# MicArraySchem_V3.net
KiCad netlist of a schematic drawn in Altium Designer
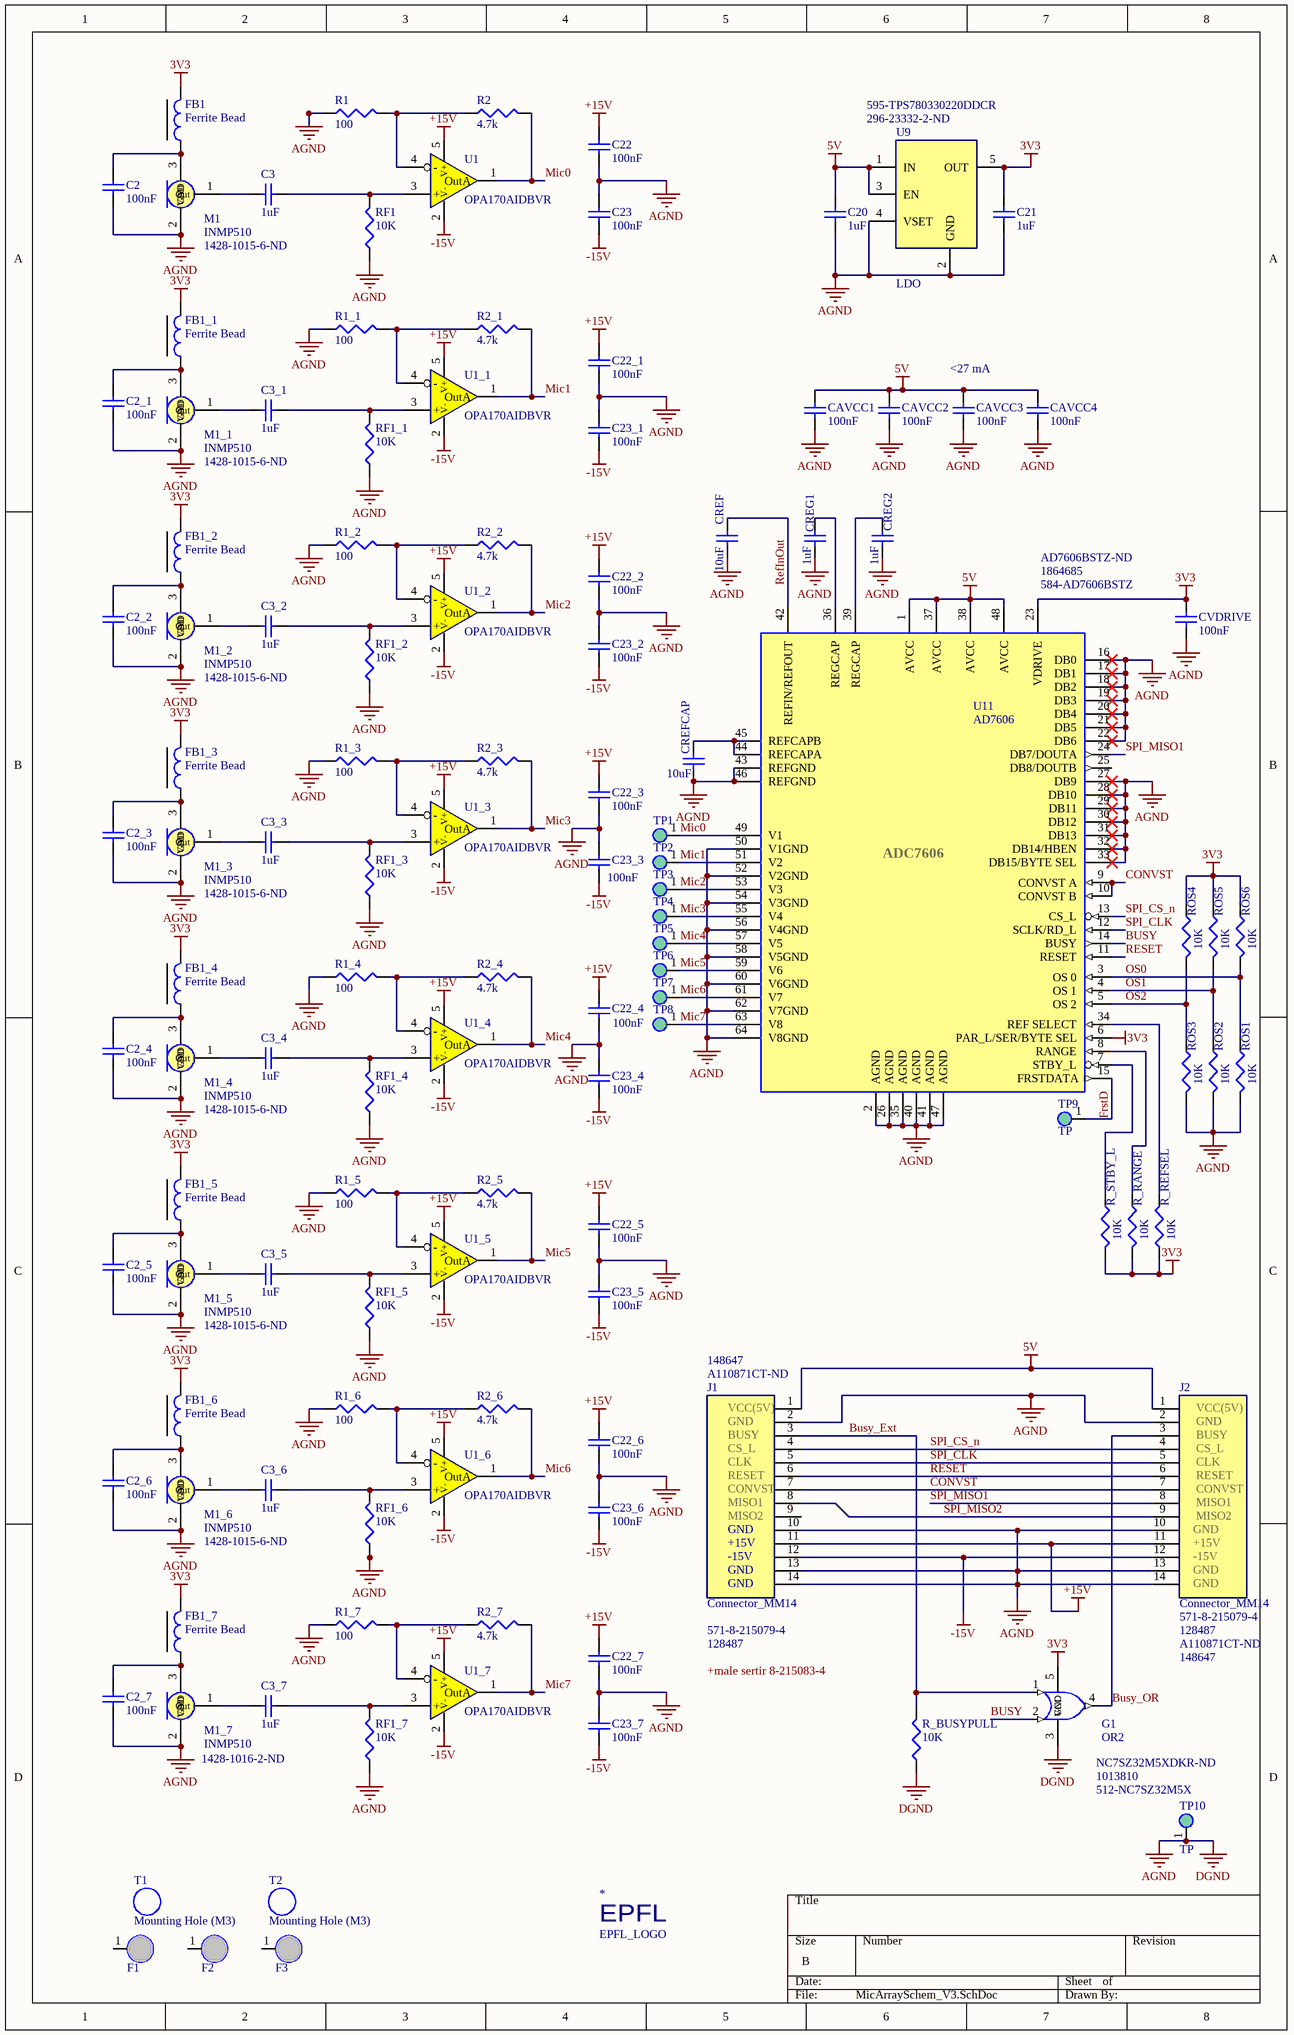
[diagram p0: MicArraySchem_V3.SchDoc]

(export (version "E")
  (design (tool "Eeschema 10.0.6"))
  (components
    (comp (ref "*")
      (value "EPFL_LOGO")
      (footprint "EPFL_Logo")
      (libsource (lib "HEPIA_LSN_RB_V1") (part "EPFL_LOGO"))
    )
    (comp (ref "C2")
      (value "100nF")
      (footprint "1608[0603]")
      (description "Capacitor (Semiconductor SIM Model)")
      (fields (field (name "PUBLISHER") "Altium Limited"))
      (libsource (lib "Miscellaneous Devices") (part "Cap Semi"))
    )
    (comp (ref "C2_1")
      (value "100nF")
      (footprint "1608[0603]")
      (description "Capacitor (Semiconductor SIM Model)")
      (fields (field (name "PUBLISHER") "Altium Limited"))
      (libsource (lib "Miscellaneous Devices") (part "Cap Semi"))
    )
    (comp (ref "C2_2")
      (value "100nF")
      (footprint "1608[0603]")
      (description "Capacitor (Semiconductor SIM Model)")
      (fields (field (name "PUBLISHER") "Altium Limited"))
      (libsource (lib "Miscellaneous Devices") (part "Cap Semi"))
    )
    (comp (ref "C2_3")
      (value "100nF")
      (footprint "1608[0603]")
      (description "Capacitor (Semiconductor SIM Model)")
      (fields (field (name "PUBLISHER") "Altium Limited"))
      (libsource (lib "Miscellaneous Devices") (part "Cap Semi"))
    )
    (comp (ref "C2_4")
      (value "100nF")
      (footprint "1608[0603]")
      (description "Capacitor (Semiconductor SIM Model)")
      (fields (field (name "PUBLISHER") "Altium Limited"))
      (libsource (lib "Miscellaneous Devices") (part "Cap Semi"))
    )
    (comp (ref "C2_5")
      (value "100nF")
      (footprint "1608[0603]")
      (description "Capacitor (Semiconductor SIM Model)")
      (fields (field (name "PUBLISHER") "Altium Limited"))
      (libsource (lib "Miscellaneous Devices") (part "Cap Semi"))
    )
    (comp (ref "C2_6")
      (value "100nF")
      (footprint "1608[0603]")
      (description "Capacitor (Semiconductor SIM Model)")
      (fields (field (name "PUBLISHER") "Altium Limited"))
      (libsource (lib "Miscellaneous Devices") (part "Cap Semi"))
    )
    (comp (ref "C2_7")
      (value "100nF")
      (footprint "1608[0603]")
      (description "Capacitor (Semiconductor SIM Model)")
      (fields (field (name "PUBLISHER") "Altium Limited"))
      (libsource (lib "Miscellaneous Devices") (part "Cap Semi"))
    )
    (comp (ref "C3")
      (value "1uF")
      (footprint "1608[0603]")
      (description "Capacitor (Semiconductor SIM Model)")
      (libsource (lib "Miscellaneous Devices") (part "Cap Semi"))
    )
    (comp (ref "C3_1")
      (value "1uF")
      (footprint "1608[0603]")
      (description "Capacitor (Semiconductor SIM Model)")
      (fields (field (name "PUBLISHER") "Altium Limited"))
      (libsource (lib "Miscellaneous Devices") (part "Cap Semi"))
    )
    (comp (ref "C3_2")
      (value "1uF")
      (footprint "1608[0603]")
      (description "Capacitor (Semiconductor SIM Model)")
      (fields (field (name "PUBLISHER") "Altium Limited"))
      (libsource (lib "Miscellaneous Devices") (part "Cap Semi"))
    )
    (comp (ref "C3_3")
      (value "1uF")
      (footprint "1608[0603]")
      (description "Capacitor (Semiconductor SIM Model)")
      (fields (field (name "PUBLISHER") "Altium Limited"))
      (libsource (lib "Miscellaneous Devices") (part "Cap Semi"))
    )
    (comp (ref "C3_4")
      (value "1uF")
      (footprint "1608[0603]")
      (description "Capacitor (Semiconductor SIM Model)")
      (fields (field (name "PUBLISHER") "Altium Limited"))
      (libsource (lib "Miscellaneous Devices") (part "Cap Semi"))
    )
    (comp (ref "C3_5")
      (value "1uF")
      (footprint "1608[0603]")
      (description "Capacitor (Semiconductor SIM Model)")
      (fields (field (name "PUBLISHER") "Altium Limited"))
      (libsource (lib "Miscellaneous Devices") (part "Cap Semi"))
    )
    (comp (ref "C3_6")
      (value "1uF")
      (footprint "1608[0603]")
      (description "Capacitor (Semiconductor SIM Model)")
      (fields (field (name "PUBLISHER") "Altium Limited"))
      (libsource (lib "Miscellaneous Devices") (part "Cap Semi"))
    )
    (comp (ref "C3_7")
      (value "1uF")
      (footprint "1608[0603]")
      (description "Capacitor (Semiconductor SIM Model)")
      (fields (field (name "PUBLISHER") "Altium Limited"))
      (libsource (lib "Miscellaneous Devices") (part "Cap Semi"))
    )
    (comp (ref "C20")
      (value "1uF")
      (footprint "1608[0603]")
      (description "Capacitor (Semiconductor SIM Model)")
      (fields (field (name "PUBLISHER") "Altium Limited"))
      (libsource (lib "Miscellaneous Devices") (part "Cap Semi"))
    )
    (comp (ref "C21")
      (value "1uF")
      (footprint "1608[0603]")
      (description "Capacitor (Semiconductor SIM Model)")
      (fields (field (name "PUBLISHER") "Altium Limited"))
      (libsource (lib "Miscellaneous Devices") (part "Cap Semi"))
    )
    (comp (ref "C22")
      (value "100nF")
      (footprint "1608[0603]")
      (description "Capacitor (Semiconductor SIM Model)")
      (fields (field (name "PUBLISHER") "Altium Limited"))
      (libsource (lib "Miscellaneous Devices") (part "Cap Semi"))
    )
    (comp (ref "C22_1")
      (value "100nF")
      (footprint "1608[0603]")
      (description "Capacitor (Semiconductor SIM Model)")
      (fields (field (name "PUBLISHER") "Altium Limited"))
      (libsource (lib "Miscellaneous Devices") (part "Cap Semi"))
    )
    (comp (ref "C22_2")
      (value "100nF")
      (footprint "1608[0603]")
      (description "Capacitor (Semiconductor SIM Model)")
      (fields (field (name "PUBLISHER") "Altium Limited"))
      (libsource (lib "Miscellaneous Devices") (part "Cap Semi"))
    )
    (comp (ref "C22_3")
      (value "100nF")
      (footprint "1608[0603]")
      (description "Capacitor (Semiconductor SIM Model)")
      (fields (field (name "PUBLISHER") "Altium Limited"))
      (libsource (lib "Miscellaneous Devices") (part "Cap Semi"))
    )
    (comp (ref "C22_4")
      (value "100nF")
      (footprint "1608[0603]")
      (description "Capacitor (Semiconductor SIM Model)")
      (fields (field (name "PUBLISHER") "Altium Limited"))
      (libsource (lib "Miscellaneous Devices") (part "Cap Semi"))
    )
    (comp (ref "C22_5")
      (value "100nF")
      (footprint "1608[0603]")
      (description "Capacitor (Semiconductor SIM Model)")
      (fields (field (name "PUBLISHER") "Altium Limited"))
      (libsource (lib "Miscellaneous Devices") (part "Cap Semi"))
    )
    (comp (ref "C22_6")
      (value "100nF")
      (footprint "1608[0603]")
      (description "Capacitor (Semiconductor SIM Model)")
      (fields (field (name "PUBLISHER") "Altium Limited"))
      (libsource (lib "Miscellaneous Devices") (part "Cap Semi"))
    )
    (comp (ref "C22_7")
      (value "100nF")
      (footprint "1608[0603]")
      (description "Capacitor (Semiconductor SIM Model)")
      (fields (field (name "PUBLISHER") "Altium Limited"))
      (libsource (lib "Miscellaneous Devices") (part "Cap Semi"))
    )
    (comp (ref "C23")
      (value "100nF")
      (footprint "1608[0603]")
      (description "Capacitor (Semiconductor SIM Model)")
      (fields (field (name "PUBLISHER") "Altium Limited"))
      (libsource (lib "Miscellaneous Devices") (part "Cap Semi"))
    )
    (comp (ref "C23_1")
      (value "100nF")
      (footprint "1608[0603]")
      (description "Capacitor (Semiconductor SIM Model)")
      (fields (field (name "PUBLISHER") "Altium Limited"))
      (libsource (lib "Miscellaneous Devices") (part "Cap Semi"))
    )
    (comp (ref "C23_2")
      (value "100nF")
      (footprint "1608[0603]")
      (description "Capacitor (Semiconductor SIM Model)")
      (fields (field (name "PUBLISHER") "Altium Limited"))
      (libsource (lib "Miscellaneous Devices") (part "Cap Semi"))
    )
    (comp (ref "C23_3")
      (value "100nF")
      (footprint "1608[0603]")
      (description "Capacitor (Semiconductor SIM Model)")
      (fields (field (name "PUBLISHER") "Altium Limited"))
      (libsource (lib "Miscellaneous Devices") (part "Cap Semi"))
    )
    (comp (ref "C23_4")
      (value "100nF")
      (footprint "1608[0603]")
      (description "Capacitor (Semiconductor SIM Model)")
      (fields (field (name "PUBLISHER") "Altium Limited"))
      (libsource (lib "Miscellaneous Devices") (part "Cap Semi"))
    )
    (comp (ref "C23_5")
      (value "100nF")
      (footprint "1608[0603]")
      (description "Capacitor (Semiconductor SIM Model)")
      (fields (field (name "PUBLISHER") "Altium Limited"))
      (libsource (lib "Miscellaneous Devices") (part "Cap Semi"))
    )
    (comp (ref "C23_6")
      (value "100nF")
      (footprint "1608[0603]")
      (description "Capacitor (Semiconductor SIM Model)")
      (fields (field (name "PUBLISHER") "Altium Limited"))
      (libsource (lib "Miscellaneous Devices") (part "Cap Semi"))
    )
    (comp (ref "C23_7")
      (value "100nF")
      (footprint "1608[0603]")
      (description "Capacitor (Semiconductor SIM Model)")
      (fields (field (name "PUBLISHER") "Altium Limited"))
      (libsource (lib "Miscellaneous Devices") (part "Cap Semi"))
    )
    (comp (ref "CAVCC1")
      (value "100nF")
      (footprint "1608[0603]")
      (description "Capacitor (Semiconductor SIM Model)")
      (fields (field (name "PUBLISHER") "Altium Limited"))
      (libsource (lib "Miscellaneous Devices") (part "Cap Semi"))
    )
    (comp (ref "CAVCC2")
      (value "100nF")
      (footprint "1608[0603]")
      (description "Capacitor (Semiconductor SIM Model)")
      (fields (field (name "PUBLISHER") "Altium Limited"))
      (libsource (lib "Miscellaneous Devices") (part "Cap Semi"))
    )
    (comp (ref "CAVCC3")
      (value "100nF")
      (footprint "1608[0603]")
      (description "Capacitor (Semiconductor SIM Model)")
      (fields (field (name "PUBLISHER") "Altium Limited"))
      (libsource (lib "Miscellaneous Devices") (part "Cap Semi"))
    )
    (comp (ref "CAVCC4")
      (value "100nF")
      (footprint "1608[0603]")
      (description "Capacitor (Semiconductor SIM Model)")
      (fields (field (name "PUBLISHER") "Altium Limited"))
      (libsource (lib "Miscellaneous Devices") (part "Cap Semi"))
    )
    (comp (ref "CREF")
      (value "10uF")
      (footprint "1608[0603]")
      (description "Capacitor (Semiconductor SIM Model)")
      (fields (field (name "PUBLISHER") "Altium Limited"))
      (libsource (lib "Miscellaneous Devices") (part "Cap Semi"))
    )
    (comp (ref "CREFCAP")
      (value "10uF")
      (footprint "1608[0603]")
      (description "Capacitor (Semiconductor SIM Model)")
      (fields (field (name "PUBLISHER") "Altium Limited"))
      (libsource (lib "Miscellaneous Devices") (part "Cap Semi"))
    )
    (comp (ref "CREG1")
      (value "1uF")
      (footprint "1608[0603]")
      (description "Capacitor (Semiconductor SIM Model)")
      (fields (field (name "PUBLISHER") "Altium Limited"))
      (libsource (lib "Miscellaneous Devices") (part "Cap Semi"))
    )
    (comp (ref "CREG2")
      (value "1uF")
      (footprint "1608[0603]")
      (description "Capacitor (Semiconductor SIM Model)")
      (fields (field (name "PUBLISHER") "Altium Limited"))
      (libsource (lib "Miscellaneous Devices") (part "Cap Semi"))
    )
    (comp (ref "CVDRIVE")
      (value "100nF")
      (footprint "1608[0603]")
      (description "Capacitor (Semiconductor SIM Model)")
      (fields (field (name "PUBLISHER") "Altium Limited"))
      (libsource (lib "Miscellaneous Devices") (part "Cap Semi"))
    )
    (comp (ref "F1") (value "*") (footprint "Fiducial_round_2mm") (libsource (lib "Lab2") (part "Reference")))
    (comp (ref "F2") (value "*") (footprint "Fiducial_round_2mm") (libsource (lib "Lab2") (part "Reference")))
    (comp (ref "F3") (value "*") (footprint "Fiducial_round_2mm") (libsource (lib "Lab2") (part "Reference")))
    (comp (ref "FB1")
      (value "Ferrite Bead")
      (footprint "HEPIA_LSN_RB_V1:L_0603")
      (description "Ferrite bead.")
      (libsource (lib "MicArraySchemComponents") (part "Ferrite Bead"))
    )
    (comp (ref "FB1_1")
      (value "Ferrite Bead")
      (footprint "L_0603")
      (description "Ferrite bead.")
      (libsource (lib "MicArraySchemComponents") (part "Ferrite Bead"))
    )
    (comp (ref "FB1_2")
      (value "Ferrite Bead")
      (footprint "L_0603")
      (description "Ferrite bead.")
      (libsource (lib "MicArraySchemComponents") (part "Ferrite Bead"))
    )
    (comp (ref "FB1_3")
      (value "Ferrite Bead")
      (footprint "L_0603")
      (description "Ferrite bead.")
      (libsource (lib "MicArraySchemComponents") (part "Ferrite Bead"))
    )
    (comp (ref "FB1_4")
      (value "Ferrite Bead")
      (footprint "L_0603")
      (description "Ferrite bead.")
      (libsource (lib "MicArraySchemComponents") (part "Ferrite Bead"))
    )
    (comp (ref "FB1_5")
      (value "Ferrite Bead")
      (footprint "L_0603")
      (description "Ferrite bead.")
      (libsource (lib "MicArraySchemComponents") (part "Ferrite Bead"))
    )
    (comp (ref "FB1_6")
      (value "Ferrite Bead")
      (footprint "L_0603")
      (description "Ferrite bead.")
      (libsource (lib "MicArraySchemComponents") (part "Ferrite Bead"))
    )
    (comp (ref "FB1_7")
      (value "Ferrite Bead")
      (footprint "L_0603")
      (description "Ferrite bead.")
      (libsource (lib "MicArraySchemComponents") (part "Ferrite Bead"))
    )
    (comp (ref "G1")
      (value "OR2")
      (footprint "SOT65P210X110-5N")
      (description "TinyOR2")
      (fields
        (field (name "SUPPLIER PART NUMBER 1") "512-NC7SZ32M5X")
        (field (name "SUPPLIER PART NUMBER 2") "1013810")
        (field (name "SUPPLIER PART NUMBER 3") "NC7SZ32M5XDKR-ND")
      )
      (libsource (lib "MicArraySchemComponents") (part "OR2"))
    )
    (comp (ref "J1")
      (value "Connector_MM14")
      (footprint "MM14 _TH_FEMALE")
      (fields
        (field (name "SUPPLIER PART NUMBER 2") "571-8-215079-4")
        (field (name "SUPPLIER PART NUMBER 4") "128487")
        (field (name "SUPPLIER PART NUMBER 3") "A110871CT-ND")
        (field (name "SUPPLIER PART NUMBER 1") "148647")
      )
      (libsource (lib "MicArraySchemComponents") (part "Connector_MM14"))
    )
    (comp (ref "J2")
      (value "Connector_MM14")
      (footprint "MM14 _TH_FEMALE")
      (fields
        (field (name "SUPPLIER PART NUMBER 2") "571-8-215079-4")
        (field (name "SUPPLIER PART NUMBER 4") "128487")
        (field (name "SUPPLIER PART NUMBER 3") "A110871CT-ND")
        (field (name "SUPPLIER PART NUMBER 1") "148647")
      )
      (libsource (lib "") (part "Connector_MM14_1"))
    )
    (comp (ref "M1")
      (value "INMP510")
      (footprint "INMP504")
      (description "INMP504")
      (fields (field (name "SUPPLIER PART NUMBER 1") "1428-1015-6-ND"))
      (libsource (lib "MicArraySchemComponents") (part "Mic"))
    )
    (comp (ref "M1_1")
      (value "INMP510")
      (footprint "INMP504")
      (description "INMP504")
      (fields (field (name "SUPPLIER PART NUMBER 1") "1428-1015-6-ND"))
      (libsource (lib "MicArraySchemComponents") (part "Mic"))
    )
    (comp (ref "M1_2")
      (value "INMP510")
      (footprint "INMP504")
      (description "INMP504")
      (fields (field (name "SUPPLIER PART NUMBER 1") "1428-1015-6-ND"))
      (libsource (lib "MicArraySchemComponents") (part "Mic"))
    )
    (comp (ref "M1_3")
      (value "INMP510")
      (footprint "INMP504")
      (description "INMP504")
      (fields (field (name "SUPPLIER PART NUMBER 1") "1428-1015-6-ND"))
      (libsource (lib "MicArraySchemComponents") (part "Mic"))
    )
    (comp (ref "M1_4")
      (value "INMP510")
      (footprint "INMP504")
      (description "INMP504")
      (fields (field (name "SUPPLIER PART NUMBER 1") "1428-1015-6-ND"))
      (libsource (lib "MicArraySchemComponents") (part "Mic"))
    )
    (comp (ref "M1_5")
      (value "INMP510")
      (footprint "INMP504")
      (description "INMP504")
      (fields (field (name "SUPPLIER PART NUMBER 1") "1428-1015-6-ND"))
      (libsource (lib "MicArraySchemComponents") (part "Mic"))
    )
    (comp (ref "M1_6")
      (value "INMP510")
      (footprint "INMP504")
      (description "INMP504")
      (fields (field (name "SUPPLIER PART NUMBER 1") "1428-1015-6-ND"))
      (libsource (lib "MicArraySchemComponents") (part "Mic"))
    )
    (comp (ref "M1_7")
      (value "INMP510")
      (footprint "INMP504")
      (description "INMP504")
      (fields (field (name "SUPPLIER PART NUMBER 1") "1428-1016-2-ND"))
      (libsource (lib "MicArraySchemComponents") (part "Mic"))
    )
    (comp (ref "R1")
      (value "100")
      (footprint "J1-0603")
      (description "Resistor")
      (fields (field (name "PUBLISHER") "Altium Limited"))
      (libsource (lib "Miscellaneous Devices") (part "Res3"))
    )
    (comp (ref "R1_1")
      (value "100")
      (footprint "J1-0603")
      (description "Resistor")
      (fields (field (name "PUBLISHER") "Altium Limited"))
      (libsource (lib "Miscellaneous Devices") (part "Res3"))
    )
    (comp (ref "R1_2")
      (value "100")
      (footprint "J1-0603")
      (description "Resistor")
      (fields (field (name "PUBLISHER") "Altium Limited"))
      (libsource (lib "Miscellaneous Devices") (part "Res3"))
    )
    (comp (ref "R1_3")
      (value "100")
      (footprint "J1-0603")
      (description "Resistor")
      (fields (field (name "PUBLISHER") "Altium Limited"))
      (libsource (lib "Miscellaneous Devices") (part "Res3"))
    )
    (comp (ref "R1_4")
      (value "100")
      (footprint "J1-0603")
      (description "Resistor")
      (fields (field (name "PUBLISHER") "Altium Limited"))
      (libsource (lib "Miscellaneous Devices") (part "Res3"))
    )
    (comp (ref "R1_5")
      (value "100")
      (footprint "J1-0603")
      (description "Resistor")
      (fields (field (name "PUBLISHER") "Altium Limited"))
      (libsource (lib "Miscellaneous Devices") (part "Res3"))
    )
    (comp (ref "R1_6")
      (value "100")
      (footprint "J1-0603")
      (description "Resistor")
      (fields (field (name "PUBLISHER") "Altium Limited"))
      (libsource (lib "Miscellaneous Devices") (part "Res3"))
    )
    (comp (ref "R1_7")
      (value "100")
      (footprint "J1-0603")
      (description "Resistor")
      (fields (field (name "PUBLISHER") "Altium Limited"))
      (libsource (lib "Miscellaneous Devices") (part "Res3"))
    )
    (comp (ref "R2")
      (value "4.7k")
      (footprint "J1-0603")
      (description "Resistor")
      (fields (field (name "PUBLISHER") "Altium Limited"))
      (libsource (lib "Miscellaneous Devices") (part "Res3"))
    )
    (comp (ref "R2_1")
      (value "4.7k")
      (footprint "J1-0603")
      (description "Resistor")
      (fields (field (name "PUBLISHER") "Altium Limited"))
      (libsource (lib "Miscellaneous Devices") (part "Res3"))
    )
    (comp (ref "R2_2")
      (value "4.7k")
      (footprint "J1-0603")
      (description "Resistor")
      (fields (field (name "PUBLISHER") "Altium Limited"))
      (libsource (lib "Miscellaneous Devices") (part "Res3"))
    )
    (comp (ref "R2_3")
      (value "4.7k")
      (footprint "J1-0603")
      (description "Resistor")
      (fields (field (name "PUBLISHER") "Altium Limited"))
      (libsource (lib "Miscellaneous Devices") (part "Res3"))
    )
    (comp (ref "R2_4")
      (value "4.7k")
      (footprint "J1-0603")
      (description "Resistor")
      (fields (field (name "PUBLISHER") "Altium Limited"))
      (libsource (lib "Miscellaneous Devices") (part "Res3"))
    )
    (comp (ref "R2_5")
      (value "4.7k")
      (footprint "J1-0603")
      (description "Resistor")
      (fields (field (name "PUBLISHER") "Altium Limited"))
      (libsource (lib "Miscellaneous Devices") (part "Res3"))
    )
    (comp (ref "R2_6")
      (value "4.7k")
      (footprint "J1-0603")
      (description "Resistor")
      (fields (field (name "PUBLISHER") "Altium Limited"))
      (libsource (lib "Miscellaneous Devices") (part "Res3"))
    )
    (comp (ref "R2_7")
      (value "4.7k")
      (footprint "J1-0603")
      (description "Resistor")
      (fields (field (name "PUBLISHER") "Altium Limited"))
      (libsource (lib "Miscellaneous Devices") (part "Res3"))
    )
    (comp (ref "RF1")
      (value "10K")
      (footprint "J1-0603")
      (description "Resistor")
      (fields (field (name "PUBLISHER") "Altium Limited"))
      (libsource (lib "Miscellaneous Devices") (part "Res3"))
    )
    (comp (ref "RF1_1")
      (value "10K")
      (footprint "J1-0603")
      (description "Resistor")
      (fields (field (name "PUBLISHER") "Altium Limited"))
      (libsource (lib "Miscellaneous Devices") (part "Res3"))
    )
    (comp (ref "RF1_2")
      (value "10K")
      (footprint "J1-0603")
      (description "Resistor")
      (fields (field (name "PUBLISHER") "Altium Limited"))
      (libsource (lib "Miscellaneous Devices") (part "Res3"))
    )
    (comp (ref "RF1_3")
      (value "10K")
      (footprint "J1-0603")
      (description "Resistor")
      (fields (field (name "PUBLISHER") "Altium Limited"))
      (libsource (lib "Miscellaneous Devices") (part "Res3"))
    )
    (comp (ref "RF1_4")
      (value "10K")
      (footprint "J1-0603")
      (description "Resistor")
      (fields (field (name "PUBLISHER") "Altium Limited"))
      (libsource (lib "Miscellaneous Devices") (part "Res3"))
    )
    (comp (ref "RF1_5")
      (value "10K")
      (footprint "J1-0603")
      (description "Resistor")
      (fields (field (name "PUBLISHER") "Altium Limited"))
      (libsource (lib "Miscellaneous Devices") (part "Res3"))
    )
    (comp (ref "RF1_6")
      (value "10K")
      (footprint "J1-0603")
      (description "Resistor")
      (fields (field (name "PUBLISHER") "Altium Limited"))
      (libsource (lib "Miscellaneous Devices") (part "Res3"))
    )
    (comp (ref "RF1_7")
      (value "10K")
      (footprint "J1-0603")
      (description "Resistor")
      (fields (field (name "PUBLISHER") "Altium Limited"))
      (libsource (lib "Miscellaneous Devices") (part "Res3"))
    )
    (comp (ref "ROS1")
      (value "10K")
      (footprint "J1-0603")
      (description "Resistor")
      (fields (field (name "PUBLISHER") "Altium Limited"))
      (libsource (lib "Miscellaneous Devices") (part "Res3"))
    )
    (comp (ref "ROS2")
      (value "10K")
      (footprint "J1-0603")
      (description "Resistor")
      (fields (field (name "PUBLISHER") "Altium Limited"))
      (libsource (lib "Miscellaneous Devices") (part "Res3"))
    )
    (comp (ref "ROS3")
      (value "10K")
      (footprint "J1-0603")
      (description "Resistor")
      (fields (field (name "PUBLISHER") "Altium Limited"))
      (libsource (lib "Miscellaneous Devices") (part "Res3"))
    )
    (comp (ref "ROS4")
      (value "10K")
      (footprint "J1-0603")
      (description "Resistor")
      (fields (field (name "PUBLISHER") "Altium Limited"))
      (libsource (lib "Miscellaneous Devices") (part "Res3"))
    )
    (comp (ref "ROS5")
      (value "10K")
      (footprint "J1-0603")
      (description "Resistor")
      (fields (field (name "PUBLISHER") "Altium Limited"))
      (libsource (lib "Miscellaneous Devices") (part "Res3"))
    )
    (comp (ref "ROS6")
      (value "10K")
      (footprint "J1-0603")
      (description "Resistor")
      (fields (field (name "PUBLISHER") "Altium Limited"))
      (libsource (lib "Miscellaneous Devices") (part "Res3"))
    )
    (comp (ref "R_BUSYPULL")
      (value "10K")
      (footprint "J1-0603")
      (description "Resistor")
      (fields (field (name "PUBLISHER") "Altium Limited"))
      (libsource (lib "Miscellaneous Devices") (part "Res3"))
    )
    (comp (ref "R_RANGE")
      (value "10K")
      (footprint "J1-0603")
      (description "Resistor")
      (fields (field (name "PUBLISHER") "Altium Limited"))
      (libsource (lib "Miscellaneous Devices") (part "Res3"))
    )
    (comp (ref "R_REFSEL")
      (value "10K")
      (footprint "J1-0603")
      (description "Resistor")
      (fields (field (name "PUBLISHER") "Altium Limited"))
      (libsource (lib "Miscellaneous Devices") (part "Res3"))
    )
    (comp (ref "R_STBY_L")
      (value "10K")
      (footprint "J1-0603")
      (description "Resistor")
      (fields (field (name "PUBLISHER") "Altium Limited"))
      (libsource (lib "Miscellaneous Devices") (part "Res3"))
    )
    (comp (ref "T1")
      (value "Mounting Hole (M3)")
      (footprint "M3MountingHole")
      (libsource (lib "MicArraySchemComponents") (part "Mounting Hole (M3)"))
    )
    (comp (ref "T2")
      (value "Mounting Hole (M3)")
      (footprint "M3MountingHole")
      (libsource (lib "MicArraySchemComponents") (part "Mounting Hole (M3)"))
    )
    (comp (ref "TP1") (value "TP") (footprint "TP_0.75mm") (libsource (lib "HEPIA_LSN_RB_V1") (part "TP")))
    (comp (ref "TP2") (value "TP") (footprint "TP_0.75mm") (libsource (lib "HEPIA_LSN_RB_V1") (part "TP")))
    (comp (ref "TP3") (value "TP") (footprint "TP_0.75mm") (libsource (lib "HEPIA_LSN_RB_V1") (part "TP")))
    (comp (ref "TP4") (value "TP") (footprint "TP_0.75mm") (libsource (lib "HEPIA_LSN_RB_V1") (part "TP")))
    (comp (ref "TP5") (value "TP") (footprint "TP_0.75mm") (libsource (lib "HEPIA_LSN_RB_V1") (part "TP")))
    (comp (ref "TP6") (value "TP") (footprint "TP_0.75mm") (libsource (lib "HEPIA_LSN_RB_V1") (part "TP")))
    (comp (ref "TP7") (value "TP") (footprint "TP_0.75mm") (libsource (lib "HEPIA_LSN_RB_V1") (part "TP")))
    (comp (ref "TP8") (value "TP") (footprint "TP_0.75mm") (libsource (lib "HEPIA_LSN_RB_V1") (part "TP")))
    (comp (ref "TP9") (value "TP") (footprint "TP_0.75mm") (libsource (lib "HEPIA_LSN_RB_V1") (part "TP")))
    (comp (ref "TP10") (value "TP") (footprint "TP_1mm") (libsource (lib "HEPIA_LSN_RB_V1") (part "TP")))
    (comp (ref "U1")
      (value "OPA170AIDBVR")
      (footprint "SOT95P280X145-5N")
      (description "OPA170")
      (libsource (lib "MicArraySchemComponents") (part "OPA170"))
    )
    (comp (ref "U1_1")
      (value "OPA170AIDBVR")
      (footprint "SOT95P280X145-5N")
      (description "OPA170")
      (libsource (lib "MicArraySchemComponents") (part "OPA170"))
    )
    (comp (ref "U1_2")
      (value "OPA170AIDBVR")
      (footprint "SOT95P280X145-5N")
      (description "OPA170")
      (libsource (lib "MicArraySchemComponents") (part "OPA170"))
    )
    (comp (ref "U1_3")
      (value "OPA170AIDBVR")
      (footprint "SOT95P280X145-5N")
      (description "OPA170")
      (libsource (lib "MicArraySchemComponents") (part "OPA170"))
    )
    (comp (ref "U1_4")
      (value "OPA170AIDBVR")
      (footprint "SOT95P280X145-5N")
      (description "OPA170")
      (libsource (lib "MicArraySchemComponents") (part "OPA170"))
    )
    (comp (ref "U1_5")
      (value "OPA170AIDBVR")
      (footprint "SOT95P280X145-5N")
      (description "OPA170")
      (libsource (lib "MicArraySchemComponents") (part "OPA170"))
    )
    (comp (ref "U1_6")
      (value "OPA170AIDBVR")
      (footprint "SOT95P280X145-5N")
      (description "OPA170")
      (libsource (lib "MicArraySchemComponents") (part "OPA170"))
    )
    (comp (ref "U1_7")
      (value "OPA170AIDBVR")
      (footprint "SOT95P280X145-5N")
      (description "OPA170")
      (libsource (lib "MicArraySchemComponents") (part "OPA170"))
    )
    (comp (ref "U9")
      (value "LDO")
      (footprint "SOT95P280X110-5N")
      (description "TPS780330220DDCR")
      (fields
        (field (name "SUPPLIER PART NUMBER 1") "296-23332-2-ND")
        (field (name "SUPPLIER PART NUMBER 2") "595-TPS780330220DDCR")
      )
      (libsource (lib "MicArraySchemComponents") (part "LDO"))
    )
    (comp (ref "U11")
      (value "AD7606")
      (footprint "LPQF-Quad64")
      (fields
        (field (name "SUPPLIER PART NUMBER 1") "AD7606BSTZ-ND")
        (field (name "SUPPLIER PART NUMBER 2") "1864685")
        (field (name "SUPPLIER PART NUMBER 3") "584-AD7606BSTZ")
      )
      (libsource (lib "MicArraySchemComponents") (part "AD7606"))
    )
  )
  (nets
    (net (code "1") (name "+15V") (class "Default")
      (node (ref "C22") (pin "1") (pinfunction "1_1") (pintype "passive"))
      (node (ref "C22_1") (pin "1") (pinfunction "1_1") (pintype "passive"))
      (node (ref "C22_2") (pin "1") (pinfunction "1_1") (pintype "passive"))
      (node (ref "C22_3") (pin "1") (pinfunction "1_1") (pintype "passive"))
      (node (ref "C22_4") (pin "1") (pinfunction "1_1") (pintype "passive"))
      (node (ref "C22_5") (pin "1") (pinfunction "1_1") (pintype "passive"))
      (node (ref "C22_6") (pin "1") (pinfunction "1_1") (pintype "passive"))
      (node (ref "C22_7") (pin "1") (pinfunction "1_1") (pintype "passive"))
      (node (ref "J1") (pin "11") (pinfunction "11_11") (pintype "passive"))
      (node (ref "J2") (pin "11") (pinfunction "11_11") (pintype "passive"))
      (node (ref "U1") (pin "5") (pinfunction "V+_5") (pintype "power_in"))
      (node (ref "U1_1") (pin "5") (pinfunction "V+_5") (pintype "power_in"))
      (node (ref "U1_2") (pin "5") (pinfunction "V+_5") (pintype "power_in"))
      (node (ref "U1_3") (pin "5") (pinfunction "V+_5") (pintype "power_in"))
      (node (ref "U1_4") (pin "5") (pinfunction "V+_5") (pintype "power_in"))
      (node (ref "U1_5") (pin "5") (pinfunction "V+_5") (pintype "power_in"))
      (node (ref "U1_6") (pin "5") (pinfunction "V+_5") (pintype "power_in"))
      (node (ref "U1_7") (pin "5") (pinfunction "V+_5") (pintype "power_in"))
    )
    (net (code "2") (name "-15V") (class "Default")
      (node (ref "C23") (pin "2") (pinfunction "2_2") (pintype "passive"))
      (node (ref "C23_1") (pin "2") (pinfunction "2_2") (pintype "passive"))
      (node (ref "C23_2") (pin "2") (pinfunction "2_2") (pintype "passive"))
      (node (ref "C23_3") (pin "2") (pinfunction "2_2") (pintype "passive"))
      (node (ref "C23_4") (pin "2") (pinfunction "2_2") (pintype "passive"))
      (node (ref "C23_5") (pin "2") (pinfunction "2_2") (pintype "passive"))
      (node (ref "C23_6") (pin "2") (pinfunction "2_2") (pintype "passive"))
      (node (ref "C23_7") (pin "2") (pinfunction "2_2") (pintype "passive"))
      (node (ref "J1") (pin "12") (pinfunction "12_12") (pintype "passive"))
      (node (ref "J2") (pin "12") (pinfunction "12_12") (pintype "passive"))
      (node (ref "U1") (pin "2") (pinfunction "V-_2") (pintype "power_in"))
      (node (ref "U1_1") (pin "2") (pinfunction "V-_2") (pintype "power_in"))
      (node (ref "U1_2") (pin "2") (pinfunction "V-_2") (pintype "power_in"))
      (node (ref "U1_3") (pin "2") (pinfunction "V-_2") (pintype "power_in"))
      (node (ref "U1_4") (pin "2") (pinfunction "V-_2") (pintype "power_in"))
      (node (ref "U1_5") (pin "2") (pinfunction "V-_2") (pintype "power_in"))
      (node (ref "U1_6") (pin "2") (pinfunction "V-_2") (pintype "power_in"))
      (node (ref "U1_7") (pin "2") (pinfunction "V-_2") (pintype "power_in"))
    )
    (net (code "3") (name "/BUSY") (class "Default")
      (node (ref "G1") (pin "2") (pintype "input"))
      (node (ref "U11") (pin "14") (pinfunction "BUSY_14") (pintype "output"))
    )
    (net (code "4") (name "/Busy_Ext") (class "Default")
      (node (ref "G1") (pin "1") (pintype "input"))
      (node (ref "J1") (pin "3") (pinfunction "3_3") (pintype "passive"))
      (node (ref "R_BUSYPULL") (pin "2") (pinfunction "2_2") (pintype "passive"))
    )
    (net (code "5") (name "/Busy_OR") (class "Default")
      (node (ref "G1") (pin "4") (pintype "output"))
      (node (ref "J2") (pin "3") (pinfunction "3_3") (pintype "passive"))
    )
    (net (code "6") (name "/CONVST") (class "Default")
      (node (ref "J1") (pin "7") (pinfunction "7_7") (pintype "passive"))
      (node (ref "J2") (pin "7") (pinfunction "7_7") (pintype "passive"))
      (node (ref "U11") (pin "10") (pinfunction "CONVST_B_10") (pintype "input"))
      (node (ref "U11") (pin "9") (pinfunction "CONVST_A_9") (pintype "input"))
    )
    (net (code "7") (name "/FrstD") (class "Default")
      (node (ref "TP9") (pin "1") (pinfunction "TP_1") (pintype "passive"))
      (node (ref "U11") (pin "15") (pinfunction "FRSTDATA_15") (pintype "output"))
    )
    (net (code "8") (name "/Mic0") (class "Default")
      (node (ref "R2") (pin "2") (pinfunction "2_2") (pintype "passive"))
      (node (ref "TP1") (pin "1") (pinfunction "TP_1") (pintype "passive"))
      (node (ref "U1") (pin "1") (pinfunction "OutA_1") (pintype "passive"))
      (node (ref "U11") (pin "49") (pinfunction "V1_49") (pintype "passive"))
    )
    (net (code "9") (name "/Mic1") (class "Default")
      (node (ref "R2_1") (pin "2") (pinfunction "2_2") (pintype "passive"))
      (node (ref "TP2") (pin "1") (pinfunction "TP_1") (pintype "passive"))
      (node (ref "U11") (pin "51") (pinfunction "V2_51") (pintype "passive"))
      (node (ref "U1_1") (pin "1") (pinfunction "OutA_1") (pintype "passive"))
    )
    (net (code "10") (name "/Mic2") (class "Default")
      (node (ref "R2_2") (pin "2") (pinfunction "2_2") (pintype "passive"))
      (node (ref "TP3") (pin "1") (pinfunction "TP_1") (pintype "passive"))
      (node (ref "U11") (pin "53") (pinfunction "V3_53") (pintype "passive"))
      (node (ref "U1_2") (pin "1") (pinfunction "OutA_1") (pintype "passive"))
    )
    (net (code "11") (name "/Mic3") (class "Default")
      (node (ref "R2_3") (pin "2") (pinfunction "2_2") (pintype "passive"))
      (node (ref "TP4") (pin "1") (pinfunction "TP_1") (pintype "passive"))
      (node (ref "U11") (pin "55") (pinfunction "V4_55") (pintype "passive"))
      (node (ref "U1_3") (pin "1") (pinfunction "OutA_1") (pintype "passive"))
    )
    (net (code "12") (name "/Mic4") (class "Default")
      (node (ref "R2_4") (pin "2") (pinfunction "2_2") (pintype "passive"))
      (node (ref "TP5") (pin "1") (pinfunction "TP_1") (pintype "passive"))
      (node (ref "U11") (pin "57") (pinfunction "V5_57") (pintype "passive"))
      (node (ref "U1_4") (pin "1") (pinfunction "OutA_1") (pintype "passive"))
    )
    (net (code "13") (name "/Mic5") (class "Default")
      (node (ref "R2_5") (pin "2") (pinfunction "2_2") (pintype "passive"))
      (node (ref "TP6") (pin "1") (pinfunction "TP_1") (pintype "passive"))
      (node (ref "U11") (pin "59") (pinfunction "V6_59") (pintype "passive"))
      (node (ref "U1_5") (pin "1") (pinfunction "OutA_1") (pintype "passive"))
    )
    (net (code "14") (name "/Mic6") (class "Default")
      (node (ref "R2_6") (pin "2") (pinfunction "2_2") (pintype "passive"))
      (node (ref "TP7") (pin "1") (pinfunction "TP_1") (pintype "passive"))
      (node (ref "U11") (pin "61") (pinfunction "V7_61") (pintype "passive"))
      (node (ref "U1_6") (pin "1") (pinfunction "OutA_1") (pintype "passive"))
    )
    (net (code "15") (name "/Mic7") (class "Default")
      (node (ref "R2_7") (pin "2") (pinfunction "2_2") (pintype "passive"))
      (node (ref "TP8") (pin "1") (pinfunction "TP_1") (pintype "passive"))
      (node (ref "U11") (pin "63") (pinfunction "V8_63") (pintype "passive"))
      (node (ref "U1_7") (pin "1") (pinfunction "OutA_1") (pintype "passive"))
    )
    (net (code "16") (name "/OS0") (class "Default")
      (node (ref "ROS1") (pin "1") (pinfunction "1_1") (pintype "passive"))
      (node (ref "ROS6") (pin "2") (pinfunction "2_2") (pintype "passive"))
      (node (ref "U11") (pin "3") (pinfunction "OS_0_3") (pintype "input"))
    )
    (net (code "17") (name "/OS1") (class "Default")
      (node (ref "ROS2") (pin "1") (pinfunction "1_1") (pintype "passive"))
      (node (ref "ROS5") (pin "2") (pinfunction "2_2") (pintype "passive"))
      (node (ref "U11") (pin "4") (pinfunction "OS_1_4") (pintype "input"))
    )
    (net (code "18") (name "/OS2") (class "Default")
      (node (ref "ROS3") (pin "1") (pinfunction "1_1") (pintype "passive"))
      (node (ref "ROS4") (pin "2") (pinfunction "2_2") (pintype "passive"))
      (node (ref "U11") (pin "5") (pinfunction "OS_2_5") (pintype "input"))
    )
    (net (code "19") (name "/RESET") (class "Default")
      (node (ref "J1") (pin "6") (pinfunction "6_6") (pintype "passive"))
      (node (ref "J2") (pin "6") (pinfunction "6_6") (pintype "passive"))
      (node (ref "U11") (pin "11") (pinfunction "RESET_11") (pintype "input"))
    )
    (net (code "20") (name "/RefInOut") (class "Default")
      (node (ref "CREF") (pin "2") (pinfunction "2_2") (pintype "passive"))
      (node (ref "U11") (pin "42") (pinfunction "REFIN/REFOUT_42") (pintype "power_in"))
    )
    (net (code "21") (name "/SPI_CLK") (class "Default")
      (node (ref "J1") (pin "5") (pinfunction "5_5") (pintype "passive"))
      (node (ref "J2") (pin "5") (pinfunction "5_5") (pintype "passive"))
      (node (ref "U11") (pin "12") (pinfunction "SCLK/RD_L_12") (pintype "input"))
    )
    (net (code "22") (name "/SPI_CS_n") (class "Default")
      (node (ref "J1") (pin "4") (pinfunction "4_4") (pintype "passive"))
      (node (ref "J2") (pin "4") (pinfunction "4_4") (pintype "passive"))
      (node (ref "U11") (pin "13") (pinfunction "CS_L_13") (pintype "input"))
    )
    (net (code "23") (name "/SPI_MISO1") (class "Default")
      (node (ref "J2") (pin "8") (pinfunction "8_8") (pintype "passive"))
      (node (ref "U11") (pin "24") (pinfunction "DB7/DOUTA_24") (pintype "output"))
    )
    (net (code "24") (name "/SPI_MISO2") (class "Default")
      (node (ref "J1") (pin "8") (pinfunction "8_8") (pintype "passive"))
      (node (ref "J2") (pin "9") (pinfunction "9_9") (pintype "passive"))
    )
    (net (code "25") (name "3V3") (class "Default")
      (node (ref "C21") (pin "2") (pinfunction "2_2") (pintype "passive"))
      (node (ref "CVDRIVE") (pin "1") (pinfunction "1_1") (pintype "passive"))
      (node (ref "FB1") (pin "2") (pintype "passive"))
      (node (ref "FB1_1") (pin "2") (pintype "passive"))
      (node (ref "FB1_2") (pin "2") (pintype "passive"))
      (node (ref "FB1_3") (pin "2") (pintype "passive"))
      (node (ref "FB1_4") (pin "2") (pintype "passive"))
      (node (ref "FB1_5") (pin "2") (pintype "passive"))
      (node (ref "FB1_6") (pin "2") (pintype "passive"))
      (node (ref "FB1_7") (pin "2") (pintype "passive"))
      (node (ref "G1") (pin "5") (pinfunction "VCC_5") (pintype "power_in"))
      (node (ref "ROS4") (pin "1") (pinfunction "1_1") (pintype "passive"))
      (node (ref "ROS5") (pin "1") (pinfunction "1_1") (pintype "passive"))
      (node (ref "ROS6") (pin "1") (pinfunction "1_1") (pintype "passive"))
      (node (ref "R_RANGE") (pin "2") (pinfunction "2_2") (pintype "passive"))
      (node (ref "R_REFSEL") (pin "1") (pinfunction "1_1") (pintype "passive"))
      (node (ref "R_STBY_L") (pin "2") (pinfunction "2_2") (pintype "passive"))
      (node (ref "U11") (pin "23") (pinfunction "VDRIVE_23") (pintype "power_in"))
      (node (ref "U11") (pin "6") (pinfunction "PAR_L/SER/BYTE_SEL_6") (pintype "input"))
      (node (ref "U9") (pin "5") (pinfunction "OUT_5") (pintype "passive"))
    )
    (net (code "26") (name "5V") (class "Default")
      (node (ref "C20") (pin "2") (pinfunction "2_2") (pintype "passive"))
      (node (ref "CAVCC1") (pin "2") (pinfunction "2_2") (pintype "passive"))
      (node (ref "CAVCC2") (pin "2") (pinfunction "2_2") (pintype "passive"))
      (node (ref "CAVCC3") (pin "2") (pinfunction "2_2") (pintype "passive"))
      (node (ref "CAVCC4") (pin "2") (pinfunction "2_2") (pintype "passive"))
      (node (ref "J1") (pin "1") (pinfunction "1_1") (pintype "passive"))
      (node (ref "J2") (pin "1") (pinfunction "1_1") (pintype "passive"))
      (node (ref "U11") (pin "1") (pinfunction "AVCC_1") (pintype "power_in"))
      (node (ref "U11") (pin "37") (pinfunction "AVCC_37") (pintype "power_in"))
      (node (ref "U11") (pin "38") (pinfunction "AVCC_38") (pintype "power_in"))
      (node (ref "U11") (pin "48") (pinfunction "AVCC_48") (pintype "power_in"))
      (node (ref "U9") (pin "1") (pinfunction "IN_1") (pintype "power_in"))
      (node (ref "U9") (pin "3") (pinfunction "EN_3") (pintype "passive"))
    )
    (net (code "27") (name "AGND") (class "Default")
      (node (ref "C2") (pin "1") (pinfunction "1_1") (pintype "passive"))
      (node (ref "C20") (pin "1") (pinfunction "1_1") (pintype "passive"))
      (node (ref "C21") (pin "1") (pinfunction "1_1") (pintype "passive"))
      (node (ref "C22") (pin "2") (pinfunction "2_2") (pintype "passive"))
      (node (ref "C22_1") (pin "2") (pinfunction "2_2") (pintype "passive"))
      (node (ref "C22_2") (pin "2") (pinfunction "2_2") (pintype "passive"))
      (node (ref "C22_3") (pin "2") (pinfunction "2_2") (pintype "passive"))
      (node (ref "C22_4") (pin "2") (pinfunction "2_2") (pintype "passive"))
      (node (ref "C22_5") (pin "2") (pinfunction "2_2") (pintype "passive"))
      (node (ref "C22_6") (pin "2") (pinfunction "2_2") (pintype "passive"))
      (node (ref "C22_7") (pin "2") (pinfunction "2_2") (pintype "passive"))
      (node (ref "C23") (pin "1") (pinfunction "1_1") (pintype "passive"))
      (node (ref "C23_1") (pin "1") (pinfunction "1_1") (pintype "passive"))
      (node (ref "C23_2") (pin "1") (pinfunction "1_1") (pintype "passive"))
      (node (ref "C23_3") (pin "1") (pinfunction "1_1") (pintype "passive"))
      (node (ref "C23_4") (pin "1") (pinfunction "1_1") (pintype "passive"))
      (node (ref "C23_5") (pin "1") (pinfunction "1_1") (pintype "passive"))
      (node (ref "C23_6") (pin "1") (pinfunction "1_1") (pintype "passive"))
      (node (ref "C23_7") (pin "1") (pinfunction "1_1") (pintype "passive"))
      (node (ref "C2_1") (pin "1") (pinfunction "1_1") (pintype "passive"))
      (node (ref "C2_2") (pin "1") (pinfunction "1_1") (pintype "passive"))
      (node (ref "C2_3") (pin "1") (pinfunction "1_1") (pintype "passive"))
      (node (ref "C2_4") (pin "1") (pinfunction "1_1") (pintype "passive"))
      (node (ref "C2_5") (pin "1") (pinfunction "1_1") (pintype "passive"))
      (node (ref "C2_6") (pin "1") (pinfunction "1_1") (pintype "passive"))
      (node (ref "C2_7") (pin "1") (pinfunction "1_1") (pintype "passive"))
      (node (ref "CAVCC1") (pin "1") (pinfunction "1_1") (pintype "passive"))
      (node (ref "CAVCC2") (pin "1") (pinfunction "1_1") (pintype "passive"))
      (node (ref "CAVCC3") (pin "1") (pinfunction "1_1") (pintype "passive"))
      (node (ref "CAVCC4") (pin "1") (pinfunction "1_1") (pintype "passive"))
      (node (ref "CREF") (pin "1") (pinfunction "1_1") (pintype "passive"))
      (node (ref "CREFCAP") (pin "1") (pinfunction "1_1") (pintype "passive"))
      (node (ref "CREG1") (pin "1") (pinfunction "1_1") (pintype "passive"))
      (node (ref "CREG2") (pin "1") (pinfunction "1_1") (pintype "passive"))
      (node (ref "CVDRIVE") (pin "2") (pinfunction "2_2") (pintype "passive"))
      (node (ref "G1") (pin "3") (pinfunction "GND_3") (pintype "power_in"))
      (node (ref "J1") (pin "10") (pinfunction "10_10") (pintype "passive"))
      (node (ref "J1") (pin "13") (pinfunction "13_13") (pintype "passive"))
      (node (ref "J1") (pin "14") (pinfunction "14_14") (pintype "passive"))
      (node (ref "J1") (pin "2") (pinfunction "2_2") (pintype "passive"))
      (node (ref "J2") (pin "10") (pinfunction "10_10") (pintype "passive"))
      (node (ref "J2") (pin "13") (pinfunction "13_13") (pintype "passive"))
      (node (ref "J2") (pin "14") (pinfunction "14_14") (pintype "passive"))
      (node (ref "J2") (pin "2") (pinfunction "2_2") (pintype "passive"))
      (node (ref "M1") (pin "2") (pinfunction "GND_2") (pintype "passive"))
      (node (ref "M1_1") (pin "2") (pinfunction "GND_2") (pintype "passive"))
      (node (ref "M1_2") (pin "2") (pinfunction "GND_2") (pintype "passive"))
      (node (ref "M1_3") (pin "2") (pinfunction "GND_2") (pintype "passive"))
      (node (ref "M1_4") (pin "2") (pinfunction "GND_2") (pintype "passive"))
      (node (ref "M1_5") (pin "2") (pinfunction "GND_2") (pintype "passive"))
      (node (ref "M1_6") (pin "2") (pinfunction "GND_2") (pintype "passive"))
      (node (ref "M1_7") (pin "2") (pinfunction "GND_2") (pintype "passive"))
      (node (ref "R1") (pin "1") (pinfunction "1_1") (pintype "passive"))
      (node (ref "R1_1") (pin "1") (pinfunction "1_1") (pintype "passive"))
      (node (ref "R1_2") (pin "1") (pinfunction "1_1") (pintype "passive"))
      (node (ref "R1_3") (pin "1") (pinfunction "1_1") (pintype "passive"))
      (node (ref "R1_4") (pin "1") (pinfunction "1_1") (pintype "passive"))
      (node (ref "R1_5") (pin "1") (pinfunction "1_1") (pintype "passive"))
      (node (ref "R1_6") (pin "1") (pinfunction "1_1") (pintype "passive"))
      (node (ref "R1_7") (pin "1") (pinfunction "1_1") (pintype "passive"))
      (node (ref "RF1") (pin "1") (pinfunction "1_1") (pintype "passive"))
      (node (ref "RF1_1") (pin "1") (pinfunction "1_1") (pintype "passive"))
      (node (ref "RF1_2") (pin "1") (pinfunction "1_1") (pintype "passive"))
      (node (ref "RF1_3") (pin "1") (pinfunction "1_1") (pintype "passive"))
      (node (ref "RF1_4") (pin "1") (pinfunction "1_1") (pintype "passive"))
      (node (ref "RF1_5") (pin "1") (pinfunction "1_1") (pintype "passive"))
      (node (ref "RF1_6") (pin "1") (pinfunction "1_1") (pintype "passive"))
      (node (ref "RF1_7") (pin "1") (pinfunction "1_1") (pintype "passive"))
      (node (ref "ROS1") (pin "2") (pinfunction "2_2") (pintype "passive"))
      (node (ref "ROS2") (pin "2") (pinfunction "2_2") (pintype "passive"))
      (node (ref "ROS3") (pin "2") (pinfunction "2_2") (pintype "passive"))
      (node (ref "R_BUSYPULL") (pin "1") (pinfunction "1_1") (pintype "passive"))
      (node (ref "TP10") (pin "1") (pinfunction "TP_1") (pintype "passive"))
      (node (ref "U11") (pin "16") (pinfunction "DB0_16") (pintype "tri_state"))
      (node (ref "U11") (pin "17") (pinfunction "DB1_17") (pintype "tri_state"))
      (node (ref "U11") (pin "18") (pinfunction "DB2_18") (pintype "tri_state"))
      (node (ref "U11") (pin "19") (pinfunction "DB3_19") (pintype "tri_state"))
      (node (ref "U11") (pin "2") (pinfunction "AGND_2") (pintype "power_in"))
      (node (ref "U11") (pin "20") (pinfunction "DB4_20") (pintype "tri_state"))
      (node (ref "U11") (pin "21") (pinfunction "DB5_21") (pintype "tri_state"))
      (node (ref "U11") (pin "22") (pinfunction "DB6_22") (pintype "tri_state"))
      (node (ref "U11") (pin "26") (pinfunction "AGND_26") (pintype "power_in"))
      (node (ref "U11") (pin "27") (pinfunction "DB9_27") (pintype "tri_state"))
      (node (ref "U11") (pin "28") (pinfunction "DB10_28") (pintype "tri_state"))
      (node (ref "U11") (pin "29") (pinfunction "DB11_29") (pintype "tri_state"))
      (node (ref "U11") (pin "30") (pinfunction "DB12_30") (pintype "tri_state"))
      (node (ref "U11") (pin "31") (pinfunction "DB13_31") (pintype "tri_state"))
      (node (ref "U11") (pin "32") (pinfunction "DB14/HBEN_32") (pintype "tri_state"))
      (node (ref "U11") (pin "33") (pinfunction "DB15/BYTE_SEL_33") (pintype "tri_state"))
      (node (ref "U11") (pin "35") (pinfunction "AGND_35") (pintype "power_in"))
      (node (ref "U11") (pin "40") (pinfunction "AGND_40") (pintype "power_in"))
      (node (ref "U11") (pin "41") (pinfunction "AGND_41") (pintype "power_in"))
      (node (ref "U11") (pin "43") (pinfunction "REFGND_43") (pintype "passive"))
      (node (ref "U11") (pin "46") (pinfunction "REFGND_46") (pintype "passive"))
      (node (ref "U11") (pin "47") (pinfunction "AGND_47") (pintype "power_in"))
      (node (ref "U11") (pin "50") (pinfunction "V1GND_50") (pintype "passive"))
      (node (ref "U11") (pin "52") (pinfunction "V2GND_52") (pintype "passive"))
      (node (ref "U11") (pin "54") (pinfunction "V3GND_54") (pintype "passive"))
      (node (ref "U11") (pin "56") (pinfunction "V4GND_56") (pintype "passive"))
      (node (ref "U11") (pin "58") (pinfunction "V5GND_58") (pintype "passive"))
      (node (ref "U11") (pin "60") (pinfunction "V6GND_60") (pintype "passive"))
      (node (ref "U11") (pin "62") (pinfunction "V7GND_62") (pintype "passive"))
      (node (ref "U11") (pin "64") (pinfunction "V8GND_64") (pintype "passive"))
      (node (ref "U9") (pin "2") (pinfunction "GND_2") (pintype "power_in"))
      (node (ref "U9") (pin "4") (pinfunction "VSET_4") (pintype "passive"))
    )
    (net (code "28") (name "Net-(CREG1-Pad2)") (class "Default")
      (node (ref "CREG1") (pin "2") (pinfunction "2_2") (pintype "passive"))
      (node (ref "U11") (pin "36") (pinfunction "REGCAP_36") (pintype "power_in"))
    )
    (net (code "29") (name "Net-(CREG2-Pad2)") (class "Default")
      (node (ref "CREG2") (pin "2") (pinfunction "2_2") (pintype "passive"))
      (node (ref "U11") (pin "39") (pinfunction "REGCAP_39") (pintype "power_in"))
    )
    (net (code "30") (name "Net-(M1-Out)") (class "Default")
      (node (ref "C3") (pin "1") (pinfunction "1_1") (pintype "passive"))
      (node (ref "M1") (pin "1") (pinfunction "Out_1") (pintype "passive"))
    )
    (net (code "31") (name "Net-(M1-VDD)") (class "Default")
      (node (ref "C2") (pin "2") (pinfunction "2_2") (pintype "passive"))
      (node (ref "FB1") (pin "1") (pintype "passive"))
      (node (ref "M1") (pin "3") (pinfunction "VDD_3") (pintype "power_in"))
    )
    (net (code "32") (name "Net-(M1_1-Out)") (class "Default")
      (node (ref "C3_1") (pin "1") (pinfunction "1_1") (pintype "passive"))
      (node (ref "M1_1") (pin "1") (pinfunction "Out_1") (pintype "passive"))
    )
    (net (code "33") (name "Net-(M1_1-VDD)") (class "Default")
      (node (ref "C2_1") (pin "2") (pinfunction "2_2") (pintype "passive"))
      (node (ref "FB1_1") (pin "1") (pintype "passive"))
      (node (ref "M1_1") (pin "3") (pinfunction "VDD_3") (pintype "power_in"))
    )
    (net (code "34") (name "Net-(M1_2-Out)") (class "Default")
      (node (ref "C3_2") (pin "1") (pinfunction "1_1") (pintype "passive"))
      (node (ref "M1_2") (pin "1") (pinfunction "Out_1") (pintype "passive"))
    )
    (net (code "35") (name "Net-(M1_2-VDD)") (class "Default")
      (node (ref "C2_2") (pin "2") (pinfunction "2_2") (pintype "passive"))
      (node (ref "FB1_2") (pin "1") (pintype "passive"))
      (node (ref "M1_2") (pin "3") (pinfunction "VDD_3") (pintype "power_in"))
    )
    (net (code "36") (name "Net-(M1_3-Out)") (class "Default")
      (node (ref "C3_3") (pin "1") (pinfunction "1_1") (pintype "passive"))
      (node (ref "M1_3") (pin "1") (pinfunction "Out_1") (pintype "passive"))
    )
    (net (code "37") (name "Net-(M1_3-VDD)") (class "Default")
      (node (ref "C2_3") (pin "2") (pinfunction "2_2") (pintype "passive"))
      (node (ref "FB1_3") (pin "1") (pintype "passive"))
      (node (ref "M1_3") (pin "3") (pinfunction "VDD_3") (pintype "power_in"))
    )
    (net (code "38") (name "Net-(M1_4-Out)") (class "Default")
      (node (ref "C3_4") (pin "1") (pinfunction "1_1") (pintype "passive"))
      (node (ref "M1_4") (pin "1") (pinfunction "Out_1") (pintype "passive"))
    )
    (net (code "39") (name "Net-(M1_4-VDD)") (class "Default")
      (node (ref "C2_4") (pin "2") (pinfunction "2_2") (pintype "passive"))
      (node (ref "FB1_4") (pin "1") (pintype "passive"))
      (node (ref "M1_4") (pin "3") (pinfunction "VDD_3") (pintype "power_in"))
    )
    (net (code "40") (name "Net-(M1_5-Out)") (class "Default")
      (node (ref "C3_5") (pin "1") (pinfunction "1_1") (pintype "passive"))
      (node (ref "M1_5") (pin "1") (pinfunction "Out_1") (pintype "passive"))
    )
    (net (code "41") (name "Net-(M1_5-VDD)") (class "Default")
      (node (ref "C2_5") (pin "2") (pinfunction "2_2") (pintype "passive"))
      (node (ref "FB1_5") (pin "1") (pintype "passive"))
      (node (ref "M1_5") (pin "3") (pinfunction "VDD_3") (pintype "power_in"))
    )
    (net (code "42") (name "Net-(M1_6-Out)") (class "Default")
      (node (ref "C3_6") (pin "1") (pinfunction "1_1") (pintype "passive"))
      (node (ref "M1_6") (pin "1") (pinfunction "Out_1") (pintype "passive"))
    )
    (net (code "43") (name "Net-(M1_6-VDD)") (class "Default")
      (node (ref "C2_6") (pin "2") (pinfunction "2_2") (pintype "passive"))
      (node (ref "FB1_6") (pin "1") (pintype "passive"))
      (node (ref "M1_6") (pin "3") (pinfunction "VDD_3") (pintype "power_in"))
    )
    (net (code "44") (name "Net-(M1_7-Out)") (class "Default")
      (node (ref "C3_7") (pin "1") (pinfunction "1_1") (pintype "passive"))
      (node (ref "M1_7") (pin "1") (pinfunction "Out_1") (pintype "passive"))
    )
    (net (code "45") (name "Net-(M1_7-VDD)") (class "Default")
      (node (ref "C2_7") (pin "2") (pinfunction "2_2") (pintype "passive"))
      (node (ref "FB1_7") (pin "1") (pintype "passive"))
      (node (ref "M1_7") (pin "3") (pinfunction "VDD_3") (pintype "power_in"))
    )
    (net (code "46") (name "Net-(U1-+)") (class "Default")
      (node (ref "C3") (pin "2") (pinfunction "2_2") (pintype "passive"))
      (node (ref "RF1") (pin "2") (pinfunction "2_2") (pintype "passive"))
      (node (ref "U1") (pin "3") (pinfunction "+_3") (pintype "passive"))
    )
    (net (code "47") (name "Net-(U1--)") (class "Default")
      (node (ref "R1") (pin "2") (pinfunction "2_2") (pintype "passive"))
      (node (ref "R2") (pin "1") (pinfunction "1_1") (pintype "passive"))
      (node (ref "U1") (pin "4") (pinfunction "-_4") (pintype "passive"))
    )
    (net (code "48") (name "Net-(U1_1-+)") (class "Default")
      (node (ref "C3_1") (pin "2") (pinfunction "2_2") (pintype "passive"))
      (node (ref "RF1_1") (pin "2") (pinfunction "2_2") (pintype "passive"))
      (node (ref "U1_1") (pin "3") (pinfunction "+_3") (pintype "passive"))
    )
    (net (code "49") (name "Net-(U1_1--)") (class "Default")
      (node (ref "R1_1") (pin "2") (pinfunction "2_2") (pintype "passive"))
      (node (ref "R2_1") (pin "1") (pinfunction "1_1") (pintype "passive"))
      (node (ref "U1_1") (pin "4") (pinfunction "-_4") (pintype "passive"))
    )
    (net (code "50") (name "Net-(U1_2-+)") (class "Default")
      (node (ref "C3_2") (pin "2") (pinfunction "2_2") (pintype "passive"))
      (node (ref "RF1_2") (pin "2") (pinfunction "2_2") (pintype "passive"))
      (node (ref "U1_2") (pin "3") (pinfunction "+_3") (pintype "passive"))
    )
    (net (code "51") (name "Net-(U1_2--)") (class "Default")
      (node (ref "R1_2") (pin "2") (pinfunction "2_2") (pintype "passive"))
      (node (ref "R2_2") (pin "1") (pinfunction "1_1") (pintype "passive"))
      (node (ref "U1_2") (pin "4") (pinfunction "-_4") (pintype "passive"))
    )
    (net (code "52") (name "Net-(U1_3-+)") (class "Default")
      (node (ref "C3_3") (pin "2") (pinfunction "2_2") (pintype "passive"))
      (node (ref "RF1_3") (pin "2") (pinfunction "2_2") (pintype "passive"))
      (node (ref "U1_3") (pin "3") (pinfunction "+_3") (pintype "passive"))
    )
    (net (code "53") (name "Net-(U1_3--)") (class "Default")
      (node (ref "R1_3") (pin "2") (pinfunction "2_2") (pintype "passive"))
      (node (ref "R2_3") (pin "1") (pinfunction "1_1") (pintype "passive"))
      (node (ref "U1_3") (pin "4") (pinfunction "-_4") (pintype "passive"))
    )
    (net (code "54") (name "Net-(U1_4-+)") (class "Default")
      (node (ref "C3_4") (pin "2") (pinfunction "2_2") (pintype "passive"))
      (node (ref "RF1_4") (pin "2") (pinfunction "2_2") (pintype "passive"))
      (node (ref "U1_4") (pin "3") (pinfunction "+_3") (pintype "passive"))
    )
    (net (code "55") (name "Net-(U1_4--)") (class "Default")
      (node (ref "R1_4") (pin "2") (pinfunction "2_2") (pintype "passive"))
      (node (ref "R2_4") (pin "1") (pinfunction "1_1") (pintype "passive"))
      (node (ref "U1_4") (pin "4") (pinfunction "-_4") (pintype "passive"))
    )
    (net (code "56") (name "Net-(U1_5-+)") (class "Default")
      (node (ref "C3_5") (pin "2") (pinfunction "2_2") (pintype "passive"))
      (node (ref "RF1_5") (pin "2") (pinfunction "2_2") (pintype "passive"))
      (node (ref "U1_5") (pin "3") (pinfunction "+_3") (pintype "passive"))
    )
    (net (code "57") (name "Net-(U1_5--)") (class "Default")
      (node (ref "R1_5") (pin "2") (pinfunction "2_2") (pintype "passive"))
      (node (ref "R2_5") (pin "1") (pinfunction "1_1") (pintype "passive"))
      (node (ref "U1_5") (pin "4") (pinfunction "-_4") (pintype "passive"))
    )
    (net (code "58") (name "Net-(U1_6-+)") (class "Default")
      (node (ref "C3_6") (pin "2") (pinfunction "2_2") (pintype "passive"))
      (node (ref "RF1_6") (pin "2") (pinfunction "2_2") (pintype "passive"))
      (node (ref "U1_6") (pin "3") (pinfunction "+_3") (pintype "passive"))
    )
    (net (code "59") (name "Net-(U1_6--)") (class "Default")
      (node (ref "R1_6") (pin "2") (pinfunction "2_2") (pintype "passive"))
      (node (ref "R2_6") (pin "1") (pinfunction "1_1") (pintype "passive"))
      (node (ref "U1_6") (pin "4") (pinfunction "-_4") (pintype "passive"))
    )
    (net (code "60") (name "Net-(U1_7-+)") (class "Default")
      (node (ref "C3_7") (pin "2") (pinfunction "2_2") (pintype "passive"))
      (node (ref "RF1_7") (pin "2") (pinfunction "2_2") (pintype "passive"))
      (node (ref "U1_7") (pin "3") (pinfunction "+_3") (pintype "passive"))
    )
    (net (code "61") (name "Net-(U1_7--)") (class "Default")
      (node (ref "R1_7") (pin "2") (pinfunction "2_2") (pintype "passive"))
      (node (ref "R2_7") (pin "1") (pinfunction "1_1") (pintype "passive"))
      (node (ref "U1_7") (pin "4") (pinfunction "-_4") (pintype "passive"))
    )
    (net (code "62") (name "Net-(U11-RANGE)") (class "Default")
      (node (ref "R_RANGE") (pin "1") (pinfunction "1_1") (pintype "passive"))
      (node (ref "U11") (pin "8") (pinfunction "RANGE_8") (pintype "input"))
    )
    (net (code "63") (name "Net-(U11-REFCAPA)") (class "Default")
      (node (ref "CREFCAP") (pin "2") (pinfunction "2_2") (pintype "passive"))
      (node (ref "U11") (pin "44") (pinfunction "REFCAPA_44") (pintype "passive"))
      (node (ref "U11") (pin "45") (pinfunction "REFCAPB_45") (pintype "passive"))
    )
    (net (code "64") (name "Net-(U11-REF_SELECT)") (class "Default")
      (node (ref "R_REFSEL") (pin "2") (pinfunction "2_2") (pintype "passive"))
      (node (ref "U11") (pin "34") (pinfunction "REF_SELECT_34") (pintype "input"))
    )
    (net (code "65") (name "Net-(U11-STBY_L)") (class "Default")
      (node (ref "R_STBY_L") (pin "1") (pinfunction "1_1") (pintype "passive"))
      (node (ref "U11") (pin "7") (pinfunction "STBY_L_7") (pintype "input"))
    )
    (net (code "66") (name "unconnected-(F1-Pad1)") (class "Default")
      (node (ref "F1") (pin "1") (pintype "passive"))
    )
    (net (code "67") (name "unconnected-(F2-Pad1)") (class "Default")
      (node (ref "F2") (pin "1") (pintype "passive"))
    )
    (net (code "68") (name "unconnected-(F3-Pad1)") (class "Default")
      (node (ref "F3") (pin "1") (pintype "passive"))
    )
    (net (code "69") (name "unconnected-(J1-Pad9)") (class "Default")
      (node (ref "J1") (pin "9") (pinfunction "9_9") (pintype "passive"))
    )
    (net (code "70") (name "unconnected-(U11-DB8{slash}DOUTB-Pad25)") (class "Default")
      (node (ref "U11") (pin "25") (pinfunction "DB8/DOUTB_25") (pintype "output"))
    )
  )
)
